# ModuleConnectorA.net
KiCad netlist of a schematic drawn in Altium Designer
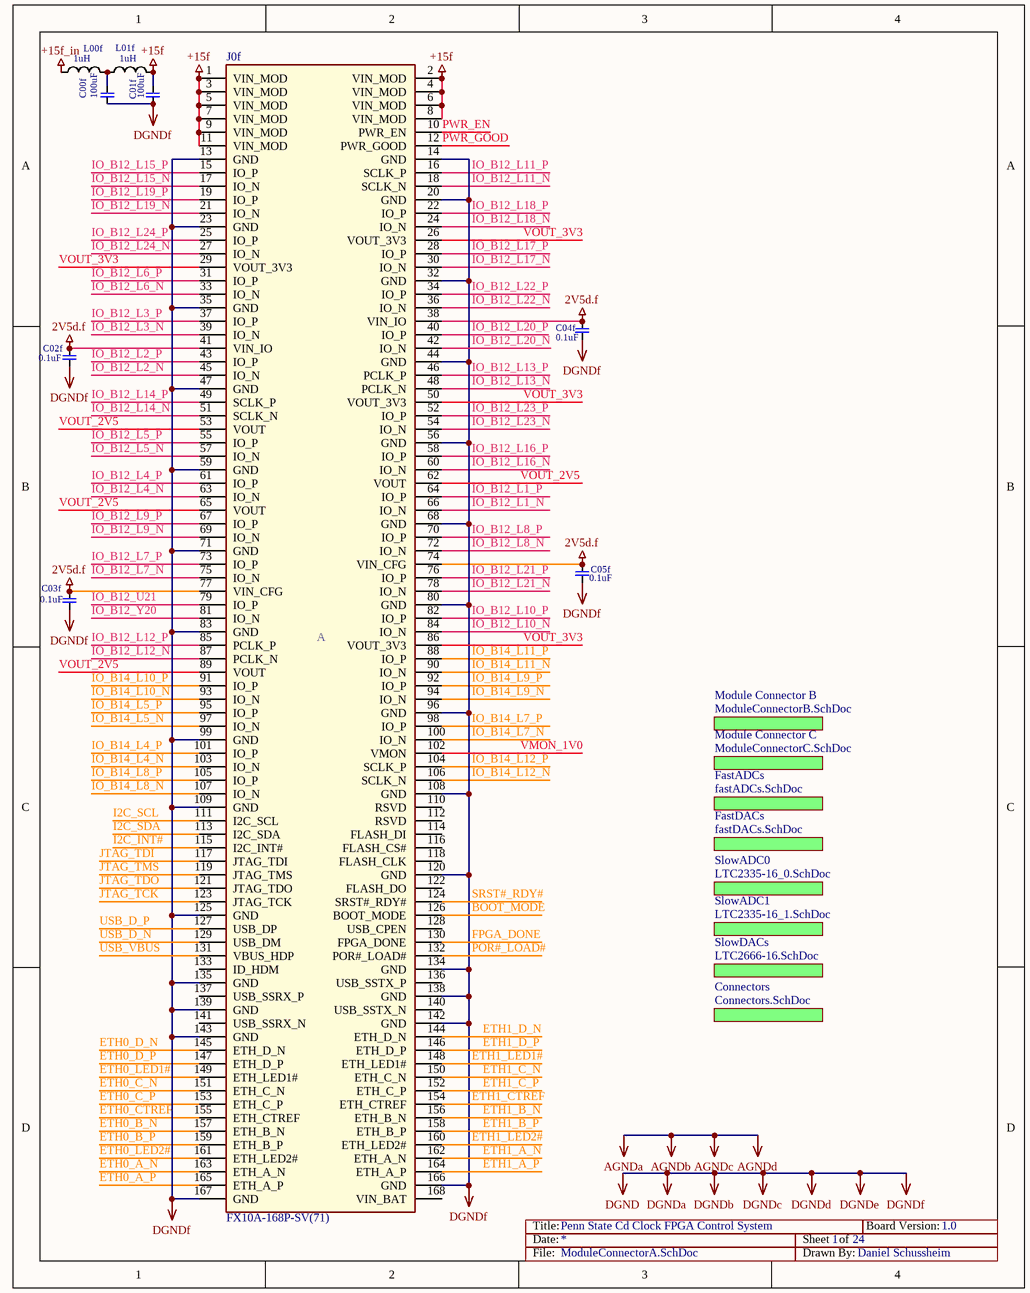
[diagram p0: ModuleConnectorA.SchDoc]

(export (version "E")
  (design (tool "Eeschema 10.0.6"))
  (components
    (comp (ref "C00f")
      (value "100uF")
      (footprint "1206")
      (libsource (lib "Mercury_AD_BaseBoard_SCHLIB") (part "CAP"))
    )
    (comp (ref "C01f")
      (value "100uF")
      (footprint "1206")
      (libsource (lib "Mercury_AD_BaseBoard_SCHLIB") (part "CAP"))
    )
    (comp (ref "C02f")
      (value "0.1uF")
      (footprint "0603")
      (libsource (lib "Mercury_AD_BaseBoard_SCHLIB") (part "CAP"))
    )
    (comp (ref "C03f")
      (value "0.1uF")
      (footprint "0603")
      (libsource (lib "Mercury_AD_BaseBoard_SCHLIB") (part "CAP"))
    )
    (comp (ref "C04f")
      (value "0.1uF")
      (footprint "0603")
      (libsource (lib "Mercury_AD_BaseBoard_SCHLIB") (part "CAP"))
    )
    (comp (ref "C05f")
      (value "0.1uF")
      (footprint "0603")
      (libsource (lib "Mercury_AD_BaseBoard_SCHLIB") (part "CAP"))
    )
    (comp (ref "J0f")
      (value "FX10A-168P-SV(71)")
      (footprint "Mercury_Baseboard_Connector")
      (description "Mercury Baseboard Connector")
      (fields
        (field (name "MANUFACTURER") "Hirose")
        (field (name "DISTPARTNUMBER") "FX10A-168P-SV(71)-ND")
        (field (name "CHECK SCH") "CG_2015-03-03")
      )
      (libsource (lib "Enclustra-Mars-Mercury-Altium-Library") (part "Mercury_Baseboard_Connector-A"))
    )
    (comp (ref "L00f")
      (value "1uH")
      (footprint "1206")
      (libsource (lib "Mercury_AD_BaseBoard_SCHLIB") (part "INDUCTOR"))
    )
    (comp (ref "L01f")
      (value "1uH")
      (footprint "1206")
      (libsource (lib "Mercury_AD_BaseBoard_SCHLIB") (part "INDUCTOR"))
    )
  )
  (nets
    (net (code "1") (name "+15f") (class "Default")
      (node (ref "C01f") (pin "1") (pintype "passive"))
      (node (ref "J0f") (pin "1") (pinfunction "VIN_MOD_1") (pintype "power_in"))
      (node (ref "J0f") (pin "11") (pinfunction "VIN_MOD_11") (pintype "power_in"))
      (node (ref "J0f") (pin "2") (pinfunction "VIN_MOD_2") (pintype "power_in"))
      (node (ref "J0f") (pin "3") (pinfunction "VIN_MOD_3") (pintype "power_in"))
      (node (ref "J0f") (pin "4") (pinfunction "VIN_MOD_4") (pintype "power_in"))
      (node (ref "J0f") (pin "5") (pinfunction "VIN_MOD_5") (pintype "power_in"))
      (node (ref "J0f") (pin "6") (pinfunction "VIN_MOD_6") (pintype "power_in"))
      (node (ref "J0f") (pin "7") (pinfunction "VIN_MOD_7") (pintype "power_in"))
      (node (ref "J0f") (pin "8") (pinfunction "VIN_MOD_8") (pintype "power_in"))
      (node (ref "J0f") (pin "9") (pinfunction "VIN_MOD_9") (pintype "power_in"))
      (node (ref "L01f") (pin "2") (pinfunction "2_2") (pintype "passive"))
    )
    (net (code "2") (name "+15f_in") (class "Default")
      (node (ref "L00f") (pin "1") (pinfunction "1_1") (pintype "passive"))
    )
    (net (code "3") (name "/BOOT_MODE") (class "Default")
      (node (ref "J0f") (pin "126") (pinfunction "BOOT_MODE_126") (pintype "passive"))
    )
    (net (code "4") (name "/ETH0_A_N") (class "Default")
      (node (ref "J0f") (pin "163") (pinfunction "ETH_A_N_163") (pintype "passive"))
    )
    (net (code "5") (name "/ETH0_A_P") (class "Default")
      (node (ref "J0f") (pin "165") (pinfunction "ETH_A_P_165") (pintype "passive"))
    )
    (net (code "6") (name "/ETH0_B_N") (class "Default")
      (node (ref "J0f") (pin "157") (pinfunction "ETH_B_N_157") (pintype "passive"))
    )
    (net (code "7") (name "/ETH0_B_P") (class "Default")
      (node (ref "J0f") (pin "159") (pinfunction "ETH_B_P_159") (pintype "passive"))
    )
    (net (code "8") (name "/ETH0_CTREF") (class "Default")
      (node (ref "J0f") (pin "155") (pinfunction "ETH_CTREF_155") (pintype "passive"))
    )
    (net (code "9") (name "/ETH0_C_N") (class "Default")
      (node (ref "J0f") (pin "151") (pinfunction "ETH_C_N_151") (pintype "passive"))
    )
    (net (code "10") (name "/ETH0_C_P") (class "Default")
      (node (ref "J0f") (pin "153") (pinfunction "ETH_C_P_153") (pintype "passive"))
    )
    (net (code "11") (name "/ETH0_D_N") (class "Default")
      (node (ref "J0f") (pin "145") (pinfunction "ETH_D_N_145") (pintype "passive"))
    )
    (net (code "12") (name "/ETH0_D_P") (class "Default")
      (node (ref "J0f") (pin "147") (pinfunction "ETH_D_P_147") (pintype "passive"))
    )
    (net (code "13") (name "/ETH0_LED1#") (class "Default")
      (node (ref "J0f") (pin "149") (pinfunction "ETH_LED1#_149") (pintype "passive"))
    )
    (net (code "14") (name "/ETH0_LED2#") (class "Default")
      (node (ref "J0f") (pin "161") (pinfunction "ETH_LED2#_161") (pintype "passive"))
    )
    (net (code "15") (name "/ETH1_A_N") (class "Default")
      (node (ref "J0f") (pin "162") (pinfunction "ETH_A_N_162") (pintype "passive"))
    )
    (net (code "16") (name "/ETH1_A_P") (class "Default")
      (node (ref "J0f") (pin "164") (pinfunction "ETH_A_P_164") (pintype "passive"))
    )
    (net (code "17") (name "/ETH1_B_N") (class "Default")
      (node (ref "J0f") (pin "156") (pinfunction "ETH_B_N_156") (pintype "passive"))
    )
    (net (code "18") (name "/ETH1_B_P") (class "Default")
      (node (ref "J0f") (pin "158") (pinfunction "ETH_B_P_158") (pintype "passive"))
    )
    (net (code "19") (name "/ETH1_CTREF") (class "Default")
      (node (ref "J0f") (pin "154") (pinfunction "ETH_CTREF_154") (pintype "passive"))
    )
    (net (code "20") (name "/ETH1_C_N") (class "Default")
      (node (ref "J0f") (pin "150") (pinfunction "ETH_C_N_150") (pintype "passive"))
    )
    (net (code "21") (name "/ETH1_C_P") (class "Default")
      (node (ref "J0f") (pin "152") (pinfunction "ETH_C_P_152") (pintype "passive"))
    )
    (net (code "22") (name "/ETH1_D_N") (class "Default")
      (node (ref "J0f") (pin "144") (pinfunction "ETH_D_N_144") (pintype "passive"))
    )
    (net (code "23") (name "/ETH1_D_P") (class "Default")
      (node (ref "J0f") (pin "146") (pinfunction "ETH_D_P_146") (pintype "passive"))
    )
    (net (code "24") (name "/ETH1_LED1#") (class "Default")
      (node (ref "J0f") (pin "148") (pinfunction "ETH_LED1#_148") (pintype "passive"))
    )
    (net (code "25") (name "/ETH1_LED2#") (class "Default")
      (node (ref "J0f") (pin "160") (pinfunction "ETH_LED2#_160") (pintype "passive"))
    )
    (net (code "26") (name "/FPGA_DONE") (class "Default")
      (node (ref "J0f") (pin "130") (pinfunction "FPGA_DONE_130") (pintype "passive"))
    )
    (net (code "27") (name "/I2C_INT#") (class "Default")
      (node (ref "J0f") (pin "115") (pinfunction "I2C_INT#_115") (pintype "passive"))
    )
    (net (code "28") (name "/I2C_SCL") (class "Default")
      (node (ref "J0f") (pin "111") (pinfunction "I2C_SCL_111") (pintype "passive"))
    )
    (net (code "29") (name "/I2C_SDA") (class "Default")
      (node (ref "J0f") (pin "113") (pinfunction "I2C_SDA_113") (pintype "passive"))
    )
    (net (code "30") (name "/IO_B12_L1_N") (class "Default")
      (node (ref "J0f") (pin "66") (pinfunction "IO_N_66") (pintype "passive"))
    )
    (net (code "31") (name "/IO_B12_L1_P") (class "Default")
      (node (ref "J0f") (pin "64") (pinfunction "IO_P_64") (pintype "passive"))
    )
    (net (code "32") (name "/IO_B12_L2_N") (class "Default")
      (node (ref "J0f") (pin "45") (pinfunction "IO_N_45") (pintype "passive"))
    )
    (net (code "33") (name "/IO_B12_L2_P") (class "Default")
      (node (ref "J0f") (pin "43") (pinfunction "IO_P_43") (pintype "passive"))
    )
    (net (code "34") (name "/IO_B12_L3_N") (class "Default")
      (node (ref "J0f") (pin "39") (pinfunction "IO_N_39") (pintype "passive"))
    )
    (net (code "35") (name "/IO_B12_L3_P") (class "Default")
      (node (ref "J0f") (pin "37") (pinfunction "IO_P_37") (pintype "passive"))
    )
    (net (code "36") (name "/IO_B12_L4_N") (class "Default")
      (node (ref "J0f") (pin "63") (pinfunction "IO_N_63") (pintype "passive"))
    )
    (net (code "37") (name "/IO_B12_L4_P") (class "Default")
      (node (ref "J0f") (pin "61") (pinfunction "IO_P_61") (pintype "passive"))
    )
    (net (code "38") (name "/IO_B12_L5_N") (class "Default")
      (node (ref "J0f") (pin "57") (pinfunction "IO_N_57") (pintype "passive"))
    )
    (net (code "39") (name "/IO_B12_L5_P") (class "Default")
      (node (ref "J0f") (pin "55") (pinfunction "IO_P_55") (pintype "passive"))
    )
    (net (code "40") (name "/IO_B12_L6_N") (class "Default")
      (node (ref "J0f") (pin "33") (pinfunction "IO_N_33") (pintype "passive"))
    )
    (net (code "41") (name "/IO_B12_L6_P") (class "Default")
      (node (ref "J0f") (pin "31") (pinfunction "IO_P_31") (pintype "passive"))
    )
    (net (code "42") (name "/IO_B12_L7_N") (class "Default")
      (node (ref "J0f") (pin "75") (pinfunction "IO_N_75") (pintype "passive"))
    )
    (net (code "43") (name "/IO_B12_L7_P") (class "Default")
      (node (ref "J0f") (pin "73") (pinfunction "IO_P_73") (pintype "passive"))
    )
    (net (code "44") (name "/IO_B12_L8_N") (class "Default")
      (node (ref "J0f") (pin "72") (pinfunction "IO_N_72") (pintype "passive"))
    )
    (net (code "45") (name "/IO_B12_L8_P") (class "Default")
      (node (ref "J0f") (pin "70") (pinfunction "IO_P_70") (pintype "passive"))
    )
    (net (code "46") (name "/IO_B12_L9_N") (class "Default")
      (node (ref "J0f") (pin "69") (pinfunction "IO_N_69") (pintype "passive"))
    )
    (net (code "47") (name "/IO_B12_L9_P") (class "Default")
      (node (ref "J0f") (pin "67") (pinfunction "IO_P_67") (pintype "passive"))
    )
    (net (code "48") (name "/IO_B12_L10_N") (class "Default")
      (node (ref "J0f") (pin "84") (pinfunction "IO_N_84") (pintype "passive"))
    )
    (net (code "49") (name "/IO_B12_L10_P") (class "Default")
      (node (ref "J0f") (pin "82") (pinfunction "IO_P_82") (pintype "passive"))
    )
    (net (code "50") (name "/IO_B12_L11_N") (class "Default")
      (node (ref "J0f") (pin "18") (pinfunction "SCLK_N_18") (pintype "passive"))
    )
    (net (code "51") (name "/IO_B12_L11_P") (class "Default")
      (node (ref "J0f") (pin "16") (pinfunction "SCLK_P_16") (pintype "passive"))
    )
    (net (code "52") (name "/IO_B12_L12_N") (class "Default")
      (node (ref "J0f") (pin "87") (pinfunction "PCLK_N_87") (pintype "passive"))
    )
    (net (code "53") (name "/IO_B12_L12_P") (class "Default")
      (node (ref "J0f") (pin "85") (pinfunction "PCLK_P_85") (pintype "passive"))
    )
    (net (code "54") (name "/IO_B12_L13_N") (class "Default")
      (node (ref "J0f") (pin "48") (pinfunction "PCLK_N_48") (pintype "passive"))
    )
    (net (code "55") (name "/IO_B12_L13_P") (class "Default")
      (node (ref "J0f") (pin "46") (pinfunction "PCLK_P_46") (pintype "passive"))
    )
    (net (code "56") (name "/IO_B12_L14_N") (class "Default")
      (node (ref "J0f") (pin "51") (pinfunction "SCLK_N_51") (pintype "passive"))
    )
    (net (code "57") (name "/IO_B12_L14_P") (class "Default")
      (node (ref "J0f") (pin "49") (pinfunction "SCLK_P_49") (pintype "passive"))
    )
    (net (code "58") (name "/IO_B12_L15_N") (class "Default")
      (node (ref "J0f") (pin "17") (pinfunction "IO_N_17") (pintype "passive"))
    )
    (net (code "59") (name "/IO_B12_L15_P") (class "Default")
      (node (ref "J0f") (pin "15") (pinfunction "IO_P_15") (pintype "passive"))
    )
    (net (code "60") (name "/IO_B12_L16_N") (class "Default")
      (node (ref "J0f") (pin "60") (pinfunction "IO_N_60") (pintype "passive"))
    )
    (net (code "61") (name "/IO_B12_L16_P") (class "Default")
      (node (ref "J0f") (pin "58") (pinfunction "IO_P_58") (pintype "passive"))
    )
    (net (code "62") (name "/IO_B12_L17_N") (class "Default")
      (node (ref "J0f") (pin "30") (pinfunction "IO_N_30") (pintype "passive"))
    )
    (net (code "63") (name "/IO_B12_L17_P") (class "Default")
      (node (ref "J0f") (pin "28") (pinfunction "IO_P_28") (pintype "passive"))
    )
    (net (code "64") (name "/IO_B12_L18_N") (class "Default")
      (node (ref "J0f") (pin "24") (pinfunction "IO_N_24") (pintype "passive"))
    )
    (net (code "65") (name "/IO_B12_L18_P") (class "Default")
      (node (ref "J0f") (pin "22") (pinfunction "IO_P_22") (pintype "passive"))
    )
    (net (code "66") (name "/IO_B12_L19_N") (class "Default")
      (node (ref "J0f") (pin "21") (pinfunction "IO_N_21") (pintype "passive"))
    )
    (net (code "67") (name "/IO_B12_L19_P") (class "Default")
      (node (ref "J0f") (pin "19") (pinfunction "IO_P_19") (pintype "passive"))
    )
    (net (code "68") (name "/IO_B12_L20_N") (class "Default")
      (node (ref "J0f") (pin "42") (pinfunction "IO_N_42") (pintype "passive"))
    )
    (net (code "69") (name "/IO_B12_L20_P") (class "Default")
      (node (ref "J0f") (pin "40") (pinfunction "IO_P_40") (pintype "passive"))
    )
    (net (code "70") (name "/IO_B12_L21_N") (class "Default")
      (node (ref "J0f") (pin "78") (pinfunction "IO_N_78") (pintype "passive"))
    )
    (net (code "71") (name "/IO_B12_L21_P") (class "Default")
      (node (ref "J0f") (pin "76") (pinfunction "IO_P_76") (pintype "passive"))
    )
    (net (code "72") (name "/IO_B12_L22_N") (class "Default")
      (node (ref "J0f") (pin "36") (pinfunction "IO_N_36") (pintype "passive"))
    )
    (net (code "73") (name "/IO_B12_L22_P") (class "Default")
      (node (ref "J0f") (pin "34") (pinfunction "IO_P_34") (pintype "passive"))
    )
    (net (code "74") (name "/IO_B12_L23_N") (class "Default")
      (node (ref "J0f") (pin "54") (pinfunction "IO_N_54") (pintype "passive"))
    )
    (net (code "75") (name "/IO_B12_L23_P") (class "Default")
      (node (ref "J0f") (pin "52") (pinfunction "IO_P_52") (pintype "passive"))
    )
    (net (code "76") (name "/IO_B12_L24_N") (class "Default")
      (node (ref "J0f") (pin "27") (pinfunction "IO_N_27") (pintype "passive"))
    )
    (net (code "77") (name "/IO_B12_L24_P") (class "Default")
      (node (ref "J0f") (pin "25") (pinfunction "IO_P_25") (pintype "passive"))
    )
    (net (code "78") (name "/IO_B12_U21") (class "Default")
      (node (ref "J0f") (pin "79") (pinfunction "IO_P_79") (pintype "passive"))
    )
    (net (code "79") (name "/IO_B12_Y20") (class "Default")
      (node (ref "J0f") (pin "81") (pinfunction "IO_N_81") (pintype "passive"))
    )
    (net (code "80") (name "/IO_B14_L4_N") (class "Default")
      (node (ref "J0f") (pin "103") (pinfunction "IO_N_103") (pintype "passive"))
    )
    (net (code "81") (name "/IO_B14_L4_P") (class "Default")
      (node (ref "J0f") (pin "101") (pinfunction "IO_P_101") (pintype "passive"))
    )
    (net (code "82") (name "/IO_B14_L5_N") (class "Default")
      (node (ref "J0f") (pin "97") (pinfunction "IO_N_97") (pintype "passive"))
    )
    (net (code "83") (name "/IO_B14_L5_P") (class "Default")
      (node (ref "J0f") (pin "95") (pinfunction "IO_P_95") (pintype "passive"))
    )
    (net (code "84") (name "/IO_B14_L7_N") (class "Default")
      (node (ref "J0f") (pin "100") (pinfunction "IO_N_100") (pintype "passive"))
    )
    (net (code "85") (name "/IO_B14_L7_P") (class "Default")
      (node (ref "J0f") (pin "98") (pinfunction "IO_P_98") (pintype "passive"))
    )
    (net (code "86") (name "/IO_B14_L8_N") (class "Default")
      (node (ref "J0f") (pin "107") (pinfunction "IO_N_107") (pintype "passive"))
    )
    (net (code "87") (name "/IO_B14_L8_P") (class "Default")
      (node (ref "J0f") (pin "105") (pinfunction "IO_P_105") (pintype "passive"))
    )
    (net (code "88") (name "/IO_B14_L9_N") (class "Default")
      (node (ref "J0f") (pin "94") (pinfunction "IO_N_94") (pintype "passive"))
    )
    (net (code "89") (name "/IO_B14_L9_P") (class "Default")
      (node (ref "J0f") (pin "92") (pinfunction "IO_P_92") (pintype "passive"))
    )
    (net (code "90") (name "/IO_B14_L10_N") (class "Default")
      (node (ref "J0f") (pin "93") (pinfunction "IO_N_93") (pintype "passive"))
    )
    (net (code "91") (name "/IO_B14_L10_P") (class "Default")
      (node (ref "J0f") (pin "91") (pinfunction "IO_P_91") (pintype "passive"))
    )
    (net (code "92") (name "/IO_B14_L11_N") (class "Default")
      (node (ref "J0f") (pin "90") (pinfunction "IO_N_90") (pintype "passive"))
    )
    (net (code "93") (name "/IO_B14_L11_P") (class "Default")
      (node (ref "J0f") (pin "88") (pinfunction "IO_P_88") (pintype "passive"))
    )
    (net (code "94") (name "/IO_B14_L12_N") (class "Default")
      (node (ref "J0f") (pin "106") (pinfunction "SCLK_N_106") (pintype "passive"))
    )
    (net (code "95") (name "/IO_B14_L12_P") (class "Default")
      (node (ref "J0f") (pin "104") (pinfunction "SCLK_P_104") (pintype "passive"))
    )
    (net (code "96") (name "/JTAG_TCK") (class "Default")
      (node (ref "J0f") (pin "123") (pinfunction "JTAG_TCK_123") (pintype "passive"))
    )
    (net (code "97") (name "/JTAG_TDI") (class "Default")
      (node (ref "J0f") (pin "117") (pinfunction "JTAG_TDI_117") (pintype "passive"))
    )
    (net (code "98") (name "/JTAG_TDO") (class "Default")
      (node (ref "J0f") (pin "121") (pinfunction "JTAG_TDO_121") (pintype "passive"))
    )
    (net (code "99") (name "/JTAG_TMS") (class "Default")
      (node (ref "J0f") (pin "119") (pinfunction "JTAG_TMS_119") (pintype "passive"))
    )
    (net (code "100") (name "/POR#_LOAD#") (class "Default")
      (node (ref "J0f") (pin "132") (pinfunction "POR#_LOAD#_132") (pintype "passive"))
    )
    (net (code "101") (name "/PWR_EN") (class "Default")
      (node (ref "J0f") (pin "10") (pinfunction "PWR_EN_10") (pintype "passive"))
    )
    (net (code "102") (name "/PWR_GOOD") (class "Default")
      (node (ref "J0f") (pin "12") (pinfunction "PWR_GOOD_12") (pintype "passive"))
    )
    (net (code "103") (name "/SRST#_RDY#") (class "Default")
      (node (ref "J0f") (pin "124") (pinfunction "SRST#_RDY#_124") (pintype "passive"))
    )
    (net (code "104") (name "/USB_D_N") (class "Default")
      (node (ref "J0f") (pin "129") (pinfunction "USB_DM_129") (pintype "passive"))
    )
    (net (code "105") (name "/USB_D_P") (class "Default")
      (node (ref "J0f") (pin "127") (pinfunction "USB_DP_127") (pintype "passive"))
    )
    (net (code "106") (name "/USB_VBUS") (class "Default")
      (node (ref "J0f") (pin "131") (pinfunction "VBUS_HDP_131") (pintype "passive"))
    )
    (net (code "107") (name "/VMON_1V0") (class "Default")
      (node (ref "J0f") (pin "102") (pinfunction "VMON_102") (pintype "passive"))
    )
    (net (code "108") (name "/VOUT_2V5") (class "Default")
      (node (ref "J0f") (pin "53") (pinfunction "VOUT_53") (pintype "power_in"))
      (node (ref "J0f") (pin "62") (pinfunction "VOUT_62") (pintype "power_in"))
      (node (ref "J0f") (pin "65") (pinfunction "VOUT_65") (pintype "power_in"))
      (node (ref "J0f") (pin "89") (pinfunction "VOUT_89") (pintype "power_in"))
    )
    (net (code "109") (name "/VOUT_3V3") (class "Default")
      (node (ref "J0f") (pin "26") (pinfunction "VOUT_3V3_26") (pintype "power_in"))
      (node (ref "J0f") (pin "29") (pinfunction "VOUT_3V3_29") (pintype "power_in"))
      (node (ref "J0f") (pin "50") (pinfunction "VOUT_3V3_50") (pintype "power_in"))
      (node (ref "J0f") (pin "86") (pinfunction "VOUT_3V3_86") (pintype "power_in"))
    )
    (net (code "110") (name "2V5d.f") (class "Default")
      (node (ref "C02f") (pin "1") (pintype "passive"))
      (node (ref "C03f") (pin "1") (pintype "passive"))
      (node (ref "C04f") (pin "1") (pintype "passive"))
      (node (ref "C05f") (pin "1") (pintype "passive"))
      (node (ref "J0f") (pin "38") (pinfunction "VIN_IO_38") (pintype "power_in"))
      (node (ref "J0f") (pin "41") (pinfunction "VIN_IO_41") (pintype "power_in"))
      (node (ref "J0f") (pin "74") (pinfunction "VIN_CFG_74") (pintype "power_in"))
      (node (ref "J0f") (pin "77") (pinfunction "VIN_CFG_77") (pintype "power_in"))
    )
    (net (code "112") (name "DGND") (class "Default")
      (node (ref "C00f") (pin "2") (pintype "passive"))
      (node (ref "C01f") (pin "2") (pintype "passive"))
      (node (ref "C02f") (pin "2") (pintype "passive"))
      (node (ref "C03f") (pin "2") (pintype "passive"))
      (node (ref "C04f") (pin "2") (pintype "passive"))
      (node (ref "C05f") (pin "2") (pintype "passive"))
      (node (ref "J0f") (pin "108") (pinfunction "GND_108") (pintype "power_in"))
      (node (ref "J0f") (pin "109") (pinfunction "GND_109") (pintype "power_in"))
      (node (ref "J0f") (pin "120") (pinfunction "GND_120") (pintype "power_in"))
      (node (ref "J0f") (pin "125") (pinfunction "GND_125") (pintype "power_in"))
      (node (ref "J0f") (pin "13") (pinfunction "GND_13") (pintype "power_in"))
      (node (ref "J0f") (pin "134") (pinfunction "GND_134") (pintype "power_in"))
      (node (ref "J0f") (pin "135") (pinfunction "GND_135") (pintype "power_in"))
      (node (ref "J0f") (pin "138") (pinfunction "GND_138") (pintype "power_in"))
      (node (ref "J0f") (pin "139") (pinfunction "GND_139") (pintype "power_in"))
      (node (ref "J0f") (pin "14") (pinfunction "GND_14") (pintype "power_in"))
      (node (ref "J0f") (pin "142") (pinfunction "GND_142") (pintype "power_in"))
      (node (ref "J0f") (pin "143") (pinfunction "GND_143") (pintype "power_in"))
      (node (ref "J0f") (pin "166") (pinfunction "GND_166") (pintype "power_in"))
      (node (ref "J0f") (pin "167") (pinfunction "GND_167") (pintype "power_in"))
      (node (ref "J0f") (pin "20") (pinfunction "GND_20") (pintype "power_in"))
      (node (ref "J0f") (pin "23") (pinfunction "GND_23") (pintype "power_in"))
      (node (ref "J0f") (pin "32") (pinfunction "GND_32") (pintype "power_in"))
      (node (ref "J0f") (pin "35") (pinfunction "GND_35") (pintype "power_in"))
      (node (ref "J0f") (pin "44") (pinfunction "GND_44") (pintype "power_in"))
      (node (ref "J0f") (pin "47") (pinfunction "GND_47") (pintype "power_in"))
      (node (ref "J0f") (pin "56") (pinfunction "GND_56") (pintype "power_in"))
      (node (ref "J0f") (pin "59") (pinfunction "GND_59") (pintype "power_in"))
      (node (ref "J0f") (pin "68") (pinfunction "GND_68") (pintype "power_in"))
      (node (ref "J0f") (pin "71") (pinfunction "GND_71") (pintype "power_in"))
      (node (ref "J0f") (pin "80") (pinfunction "GND_80") (pintype "power_in"))
      (node (ref "J0f") (pin "83") (pinfunction "GND_83") (pintype "power_in"))
      (node (ref "J0f") (pin "96") (pinfunction "GND_96") (pintype "power_in"))
      (node (ref "J0f") (pin "99") (pinfunction "GND_99") (pintype "power_in"))
    )
    (net (code "113") (name "Net-(C00f-Pad1)") (class "Default")
      (node (ref "C00f") (pin "1") (pintype "passive"))
      (node (ref "L00f") (pin "2") (pinfunction "2_2") (pintype "passive"))
      (node (ref "L01f") (pin "1") (pinfunction "1_1") (pintype "passive"))
    )
    (net (code "114") (name "unconnected-(J0f-FLASH_CLK-Pad118)") (class "Default")
      (node (ref "J0f") (pin "118") (pinfunction "FLASH_CLK_118") (pintype "passive"))
    )
    (net (code "115") (name "unconnected-(J0f-FLASH_CS#-Pad116)") (class "Default")
      (node (ref "J0f") (pin "116") (pinfunction "FLASH_CS#_116") (pintype "passive"))
    )
    (net (code "116") (name "unconnected-(J0f-FLASH_DI-Pad114)") (class "Default")
      (node (ref "J0f") (pin "114") (pinfunction "FLASH_DI_114") (pintype "passive"))
    )
    (net (code "117") (name "unconnected-(J0f-FLASH_DO-Pad122)") (class "Default")
      (node (ref "J0f") (pin "122") (pinfunction "FLASH_DO_122") (pintype "passive"))
    )
    (net (code "118") (name "unconnected-(J0f-ID_HDM-Pad133)") (class "Default")
      (node (ref "J0f") (pin "133") (pinfunction "ID_HDM_133") (pintype "passive"))
    )
    (net (code "119") (name "unconnected-(J0f-RSVD-Pad110)") (class "Default")
      (node (ref "J0f") (pin "110") (pinfunction "RSVD_110") (pintype "passive"))
    )
    (net (code "120") (name "unconnected-(J0f-RSVD-Pad112)") (class "Default")
      (node (ref "J0f") (pin "112") (pinfunction "RSVD_112") (pintype "passive"))
    )
    (net (code "121") (name "unconnected-(J0f-USB_CPEN-Pad128)") (class "Default")
      (node (ref "J0f") (pin "128") (pinfunction "USB_CPEN_128") (pintype "passive"))
    )
    (net (code "122") (name "unconnected-(J0f-USB_SSRX_N-Pad141)") (class "Default")
      (node (ref "J0f") (pin "141") (pinfunction "USB_SSRX_N_141") (pintype "passive"))
    )
    (net (code "123") (name "unconnected-(J0f-USB_SSRX_P-Pad137)") (class "Default")
      (node (ref "J0f") (pin "137") (pinfunction "USB_SSRX_P_137") (pintype "passive"))
    )
    (net (code "124") (name "unconnected-(J0f-USB_SSTX_N-Pad140)") (class "Default")
      (node (ref "J0f") (pin "140") (pinfunction "USB_SSTX_N_140") (pintype "passive"))
    )
    (net (code "125") (name "unconnected-(J0f-USB_SSTX_P-Pad136)") (class "Default")
      (node (ref "J0f") (pin "136") (pinfunction "USB_SSTX_P_136") (pintype "passive"))
    )
    (net (code "126") (name "unconnected-(J0f-VIN_BAT-Pad168)") (class "Default")
      (node (ref "J0f") (pin "168") (pinfunction "VIN_BAT_168") (pintype "power_in"))
    )
  )
)
